# pepper-8m.net
KiCad netlist of a schematic drawn in EAGLE
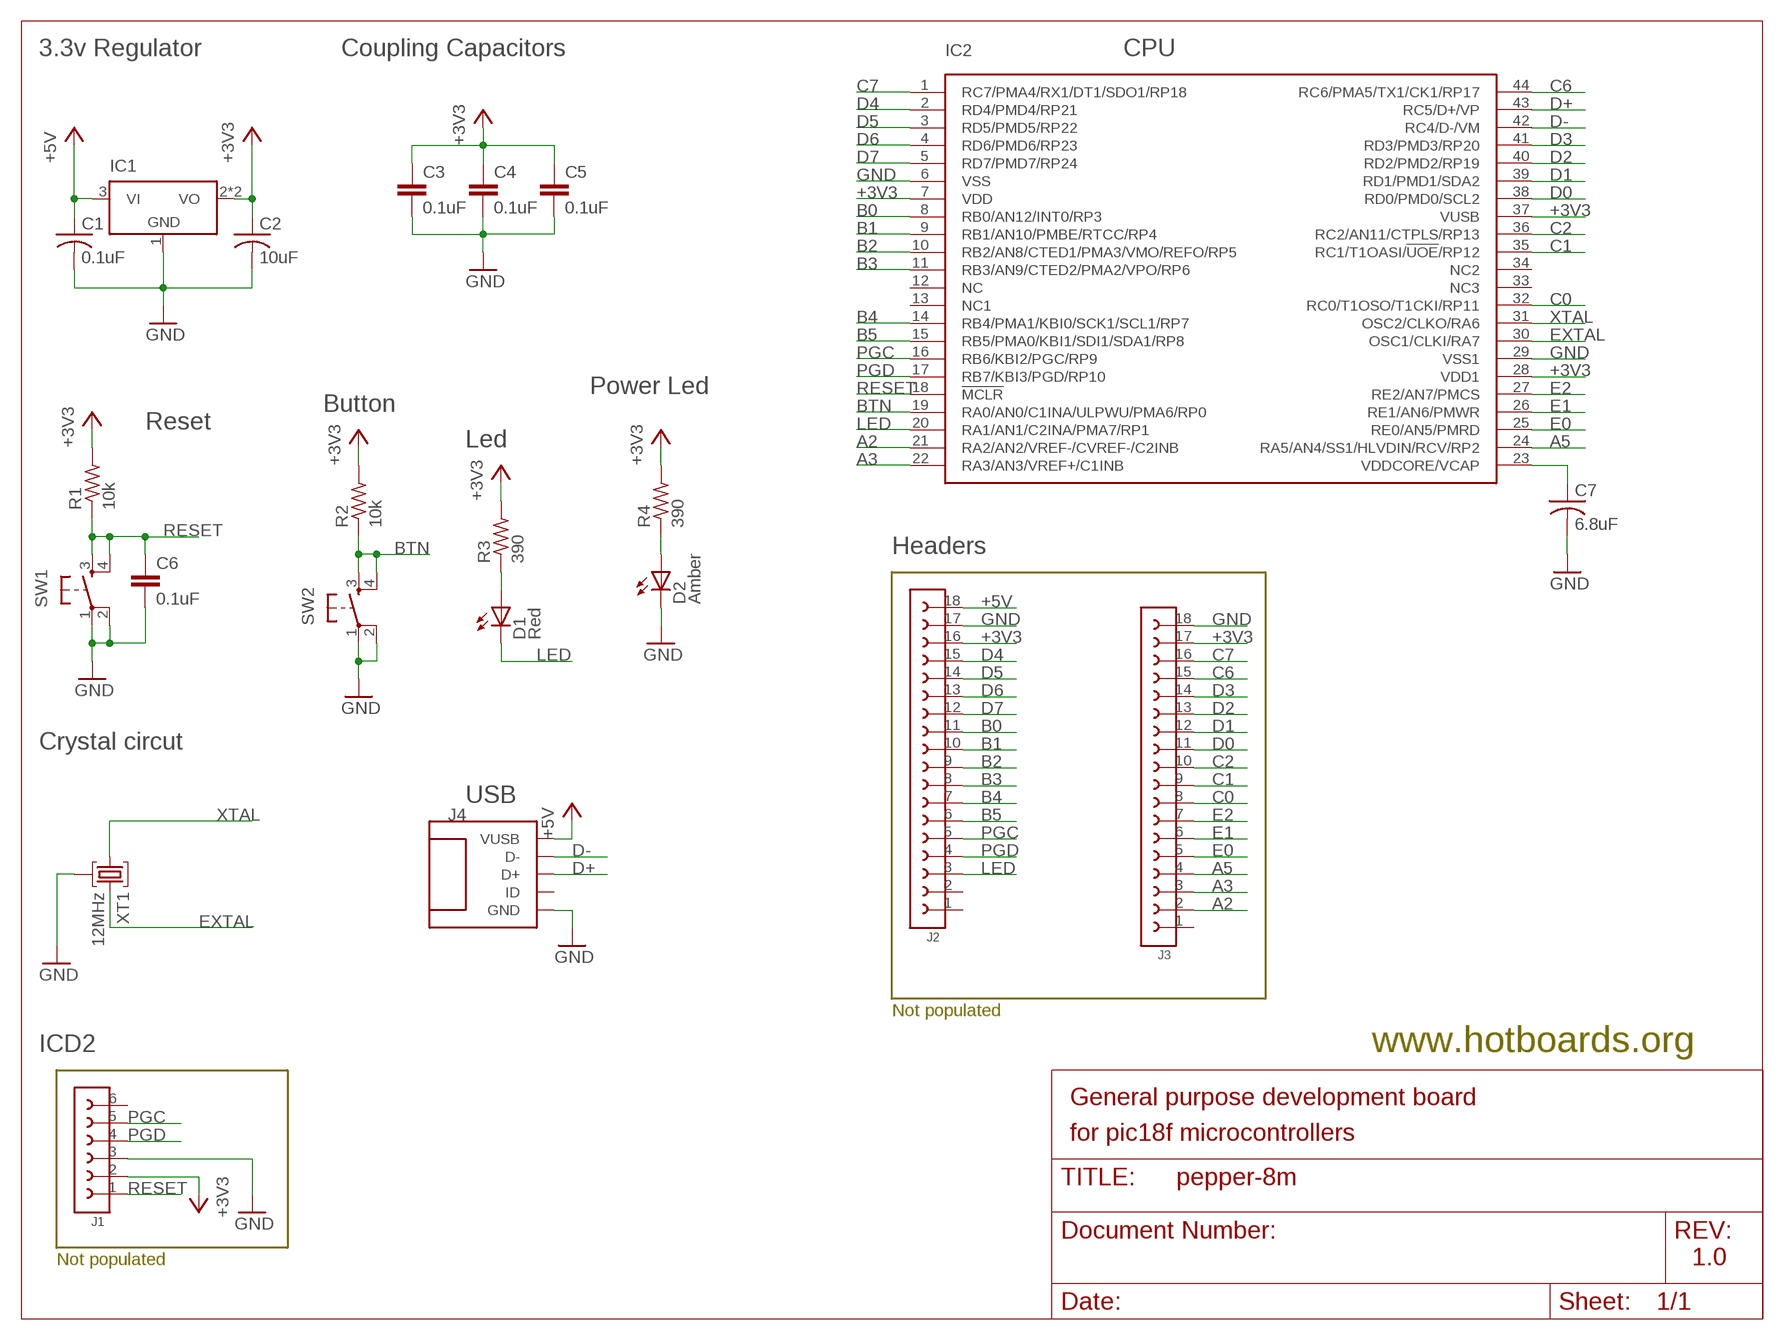
[diagram p0: schematic, sheet 1]

(export (version "E")
  (design (tool "Eeschema 10.0.6"))
  (components
    (comp (ref "C1")
      (value "0.1uF")
      (footprint "eagle-import:CAPMP3216-18")
      (fields (field (name "MANUFACTURER") "KEMET") (field (name "EAGLEUP") "CAPMP3216-18"))
      (libsource (lib "eagle-import") (part "T491?A104K050AT"))
    )
    (comp (ref "C2")
      (value "10uF")
      (footprint "eagle-import:CAPMP3216-18")
      (fields (field (name "MANUFACTURER") "KEMET") (field (name "EAGLEUP") "CAPMP3216-18"))
      (libsource (lib "eagle-import") (part "T491?A106K016AT"))
    )
    (comp (ref "C3")
      (value "0.1uF")
      (footprint "eagle-import:CAPC0603")
      (fields (field (name "MANUFACTURER") "KEMET"))
      (libsource (lib "eagle-import") (part "C?CVAC0603104Z3"))
    )
    (comp (ref "C4")
      (value "0.1uF")
      (footprint "eagle-import:CAPC0603")
      (fields (field (name "MANUFACTURER") "KEMET"))
      (libsource (lib "eagle-import") (part "C?CVAC0603104Z3"))
    )
    (comp (ref "C5")
      (value "0.1uF")
      (footprint "eagle-import:CAPC0603")
      (fields (field (name "MANUFACTURER") "KEMET"))
      (libsource (lib "eagle-import") (part "C?CVAC0603104Z3"))
    )
    (comp (ref "C6")
      (value "0.1uF")
      (footprint "eagle-import:CAPC0603")
      (description "Capacitores cerámicos de capas múltiples (MLCC) - SMD/SMT0603 25volts 0.1uF Y5V -20+80%")
      (fields
        (field (name "MANUFACTURER") "KEMET")
        (field (name "AVNET") "C0603C104Z3VAC TU")
        (field (name "AVRG-PRICE") "0.1")
        (field (name "DIGIKEY") "399-1100-2-ND")
        (field (name "EAGLEUP") "CAPC0603")
        (field (name "MANUFACTURER_1") "KEMET")
        (field (name "MOUSER") "80-C0603C104Z3V")
        (field (name "NEWARK") "31C9013")
        (field (name "OCTOPART-LINK") "http://octopart.com/c0603c104z3vactu-kemet-98662")
      )
      (libsource (lib "eagle-import") (part "C?CVAC0603104Z3"))
    )
    (comp (ref "C7")
      (value "6.8uF")
      (footprint "eagle-import:CAPMP3216-18")
      (fields (field (name "MANUFACTURER") "KEMET") (field (name "EAGLEUP") "CAPMP3216-18"))
      (libsource (lib "eagle-import") (part "T491?A685M006AT"))
    )
    (comp (ref "D1")
      (value "Red")
      (footprint "eagle-import:D0805")
      (libsource (lib "eagle-import") (part "SM0805AC"))
    )
    (comp (ref "D2")
      (value "Amber")
      (footprint "eagle-import:D0805")
      (libsource (lib "eagle-import") (part "SM0805HC"))
    )
    (comp (ref "IC1")
      (value "LD1117S33TR")
      (footprint "eagle-import:SOT230P700X180-4N")
      (fields (field (name "MANUFACTURER") "ST") (field (name "EAGLEUP") "SOT230P700X180-4N"))
      (libsource (lib "eagle-import") (part "LD1117?S33TR"))
    )
    (comp (ref "IC2")
      (value "PIC18F45J50-I/PT'")
      (footprint "eagle-import:TQFP80P1200X1200X100-44N")
      (fields (field (name "MANUFACTURER") "MICROCHIP") (field (name "EAGLEUP") "QFP80P1200X1200X100-44N"))
      (libsource (lib "eagle-import") (part "PIC18F4J50-I/PT'5"))
    )
    (comp (ref "J1")
      (value "61300611121")
      (footprint "eagle-import:PHSP254P1524X254X1154-6S")
      (fields (field (name "MANUFACTURER") "WURTH") (field (name "EAGLEUP") "PHSP254P1524X254X1154-6S"))
      (libsource (lib "eagle-import") (part "6130061?1121"))
    )
    (comp (ref "J2")
      (value "61301811121")
      (footprint "eagle-import:PHSP254P4572X254X1154-18S")
      (libsource (lib "eagle-import") (part "6130181?1121"))
    )
    (comp (ref "J3")
      (value "61301811121")
      (footprint "eagle-import:PHSP254P4572X254X1154-18S")
      (libsource (lib "eagle-import") (part "6130181?1121"))
    )
    (comp (ref "J4")
      (value "-1734035-1")
      (footprint "eagle-import:USB-MINIB-SMD+SMD+RET")
      (libsource (lib "eagle-import") (part "?-1734035-1"))
    )
    (comp (ref "R1")
      (value "10k")
      (footprint "eagle-import:RESC0603")
      (libsource (lib "eagle-import") (part "CRG?0603F10K10"))
    )
    (comp (ref "R2")
      (value "10k")
      (footprint "eagle-import:RESC0603")
      (libsource (lib "eagle-import") (part "CRG?0603F10K10"))
    )
    (comp (ref "R3")
      (value "390")
      (footprint "eagle-import:RESC0603")
      (libsource (lib "eagle-import") (part "CRG?0603F390R"))
    )
    (comp (ref "R4")
      (value "390")
      (footprint "eagle-import:RESC0603")
      (libsource (lib "eagle-import") (part "CRG?0603F390R"))
    )
    (comp (ref "SW1")
      (value "TL3301NF160QJ")
      (footprint "eagle-import:TACT600X600-4J")
      (fields (field (name "MANUFACTURER") "E-SWITCH"))
      (libsource (lib "eagle-import") (part "TL3301?JNF160Q"))
    )
    (comp (ref "SW2")
      (value "TL3301NF160QJ")
      (footprint "eagle-import:TACT600X600-4J")
      (fields (field (name "MANUFACTURER") "E-SWITCH"))
      (libsource (lib "eagle-import") (part "TL3301?JNF160Q"))
    )
    (comp (ref "XT1")
      (value "12MHz")
      (footprint "eagle-import:CERAMIC460X200-3N")
      (fields (field (name "MANUFACTURER") "ABRACON"))
      (libsource (lib "eagle-import") (part "AWSCR-CR-C12.00"))
    )
  )
  (nets
    (net (code "1") (name "+3V3") (class "Default")
      (node (ref "C2") (pin "1") (pinfunction "1_1") (pintype "passive"))
      (node (ref "C3") (pin "1") (pinfunction "1_1") (pintype "passive"))
      (node (ref "C4") (pin "1") (pinfunction "1_1") (pintype "passive"))
      (node (ref "C5") (pin "1") (pinfunction "1_1") (pintype "passive"))
      (node (ref "IC1") (pin "2") (pinfunction "VO_2") (pintype "input"))
      (node (ref "IC1") (pin "4") (pinfunction "VO_4") (pintype "input"))
      (node (ref "IC2") (pin "28") (pinfunction "VDD1_28") (pintype "power_in"))
      (node (ref "IC2") (pin "37") (pinfunction "VUSB_37") (pintype "power_in"))
      (node (ref "IC2") (pin "7") (pinfunction "VDD_7") (pintype "power_in"))
      (node (ref "J1") (pin "2") (pinfunction "2_2") (pintype "passive"))
      (node (ref "J2") (pin "16") (pinfunction "16_16") (pintype "passive"))
      (node (ref "J3") (pin "17") (pinfunction "17_17") (pintype "passive"))
      (node (ref "R1") (pin "P$2") (pinfunction "2_P$2") (pintype "passive"))
      (node (ref "R2") (pin "P$2") (pinfunction "2_P$2") (pintype "passive"))
      (node (ref "R3") (pin "P$2") (pinfunction "2_P$2") (pintype "passive"))
      (node (ref "R4") (pin "P$2") (pinfunction "2_P$2") (pintype "passive"))
    )
    (net (code "2") (name "+5V") (class "Default")
      (node (ref "C1") (pin "1") (pinfunction "1_1") (pintype "passive"))
      (node (ref "IC1") (pin "3") (pinfunction "VI_3") (pintype "input"))
      (node (ref "J2") (pin "18") (pinfunction "18_18") (pintype "passive"))
      (node (ref "J4") (pin "1") (pinfunction "VUSB_1") (pintype "bidirectional"))
    )
    (net (code "3") (name "/A2") (class "Default")
      (node (ref "IC2") (pin "21") (pinfunction "RA2/AN2/VREF-/CVREF-/C2INB_21") (pintype "bidirectional"))
      (node (ref "J3") (pin "2") (pinfunction "2_2") (pintype "passive"))
    )
    (net (code "4") (name "/A3") (class "Default")
      (node (ref "IC2") (pin "22") (pinfunction "RA3/AN3/VREF+/C1INB_22") (pintype "bidirectional"))
      (node (ref "J3") (pin "3") (pinfunction "3_3") (pintype "passive"))
    )
    (net (code "5") (name "/A5") (class "Default")
      (node (ref "IC2") (pin "24") (pinfunction "RA5/AN4/SS1/HLVDIN/RCV/RP2_24") (pintype "bidirectional"))
      (node (ref "J3") (pin "4") (pinfunction "4_4") (pintype "passive"))
    )
    (net (code "6") (name "/B0") (class "Default")
      (node (ref "IC2") (pin "8") (pinfunction "RB0/AN12/INT0/RP3_8") (pintype "bidirectional"))
      (node (ref "J2") (pin "11") (pinfunction "11_11") (pintype "passive"))
    )
    (net (code "7") (name "/B1") (class "Default")
      (node (ref "IC2") (pin "9") (pinfunction "RB1/AN10/PMBE/RTCC/RP4_9") (pintype "bidirectional"))
      (node (ref "J2") (pin "10") (pinfunction "10_10") (pintype "passive"))
    )
    (net (code "8") (name "/B2") (class "Default")
      (node (ref "IC2") (pin "10") (pinfunction "RB2/AN8/CTED1/PMA3/VMO/REFO/RP5_10") (pintype "bidirectional"))
      (node (ref "J2") (pin "9") (pinfunction "9_9") (pintype "passive"))
    )
    (net (code "9") (name "/B3") (class "Default")
      (node (ref "IC2") (pin "11") (pinfunction "RB3/AN9/CTED2/PMA2/VPO/RP6_11") (pintype "bidirectional"))
      (node (ref "J2") (pin "8") (pinfunction "8_8") (pintype "passive"))
    )
    (net (code "10") (name "/B4") (class "Default")
      (node (ref "IC2") (pin "14") (pinfunction "RB4/PMA1/KBI0/SCK1/SCL1/RP7_14") (pintype "bidirectional"))
      (node (ref "J2") (pin "7") (pinfunction "7_7") (pintype "passive"))
    )
    (net (code "11") (name "/B5") (class "Default")
      (node (ref "IC2") (pin "15") (pinfunction "RB5/PMA0/KBI1/SDI1/SDA1/RP8_15") (pintype "bidirectional"))
      (node (ref "J2") (pin "6") (pinfunction "6_6") (pintype "passive"))
    )
    (net (code "12") (name "/BTN") (class "Default")
      (node (ref "IC2") (pin "19") (pinfunction "RA0/AN0/C1INA/ULPWU/PMA6/RP0_19") (pintype "bidirectional"))
      (node (ref "R2") (pin "P$1") (pinfunction "1_P$1") (pintype "passive"))
      (node (ref "SW2") (pin "3") (pinfunction "S_3") (pintype "passive"))
      (node (ref "SW2") (pin "4") (pinfunction "S1_4") (pintype "passive"))
    )
    (net (code "13") (name "/C0") (class "Default")
      (node (ref "IC2") (pin "32") (pinfunction "RC0/T1OSO/T1CKI/RP11_32") (pintype "bidirectional"))
      (node (ref "J3") (pin "8") (pinfunction "8_8") (pintype "passive"))
    )
    (net (code "14") (name "/C1") (class "Default")
      (node (ref "IC2") (pin "35") (pinfunction "RC1/T1OASI/~{UOE}/RP12_35") (pintype "bidirectional"))
      (node (ref "J3") (pin "9") (pinfunction "9_9") (pintype "passive"))
    )
    (net (code "15") (name "/C2") (class "Default")
      (node (ref "IC2") (pin "36") (pinfunction "RC2/AN11/CTPLS/RP13_36") (pintype "bidirectional"))
      (node (ref "J3") (pin "10") (pinfunction "10_10") (pintype "passive"))
    )
    (net (code "16") (name "/C6") (class "Default")
      (node (ref "IC2") (pin "44") (pinfunction "RC6/PMA5/TX1/CK1/RP17_44") (pintype "bidirectional"))
      (node (ref "J3") (pin "15") (pinfunction "15_15") (pintype "passive"))
    )
    (net (code "17") (name "/C7") (class "Default")
      (node (ref "IC2") (pin "1") (pinfunction "RC7/PMA4/RX1/DT1/SDO1/RP18_1") (pintype "bidirectional"))
      (node (ref "J3") (pin "16") (pinfunction "16_16") (pintype "passive"))
    )
    (net (code "18") (name "/D+") (class "Default")
      (node (ref "IC2") (pin "43") (pinfunction "RC5/D+/VP_43") (pintype "bidirectional"))
      (node (ref "J4") (pin "3") (pinfunction "D+_3") (pintype "bidirectional"))
    )
    (net (code "19") (name "/D-") (class "Default")
      (node (ref "IC2") (pin "42") (pinfunction "RC4/D-/VM_42") (pintype "bidirectional"))
      (node (ref "J4") (pin "2") (pinfunction "D-_2") (pintype "bidirectional"))
    )
    (net (code "20") (name "/D0") (class "Default")
      (node (ref "IC2") (pin "38") (pinfunction "RD0/PMD0/SCL2_38") (pintype "bidirectional"))
      (node (ref "J3") (pin "11") (pinfunction "11_11") (pintype "passive"))
    )
    (net (code "21") (name "/D1") (class "Default")
      (node (ref "IC2") (pin "39") (pinfunction "RD1/PMD1/SDA2_39") (pintype "bidirectional"))
      (node (ref "J3") (pin "12") (pinfunction "12_12") (pintype "passive"))
    )
    (net (code "22") (name "/D2") (class "Default")
      (node (ref "IC2") (pin "40") (pinfunction "RD2/PMD2/RP19_40") (pintype "bidirectional"))
      (node (ref "J3") (pin "13") (pinfunction "13_13") (pintype "passive"))
    )
    (net (code "23") (name "/D3") (class "Default")
      (node (ref "IC2") (pin "41") (pinfunction "RD3/PMD3/RP20_41") (pintype "bidirectional"))
      (node (ref "J3") (pin "14") (pinfunction "14_14") (pintype "passive"))
    )
    (net (code "24") (name "/D4") (class "Default")
      (node (ref "IC2") (pin "2") (pinfunction "RD4/PMD4/RP21_2") (pintype "bidirectional"))
      (node (ref "J2") (pin "15") (pinfunction "15_15") (pintype "passive"))
    )
    (net (code "25") (name "/D5") (class "Default")
      (node (ref "IC2") (pin "3") (pinfunction "RD5/PMD5/RP22_3") (pintype "bidirectional"))
      (node (ref "J2") (pin "14") (pinfunction "14_14") (pintype "passive"))
    )
    (net (code "26") (name "/D6") (class "Default")
      (node (ref "IC2") (pin "4") (pinfunction "RD6/PMD6/RP23_4") (pintype "bidirectional"))
      (node (ref "J2") (pin "13") (pinfunction "13_13") (pintype "passive"))
    )
    (net (code "27") (name "/D7") (class "Default")
      (node (ref "IC2") (pin "5") (pinfunction "RD7/PMD7/RP24_5") (pintype "bidirectional"))
      (node (ref "J2") (pin "12") (pinfunction "12_12") (pintype "passive"))
    )
    (net (code "28") (name "/E0") (class "Default")
      (node (ref "IC2") (pin "25") (pinfunction "RE0/AN5/PMRD_25") (pintype "bidirectional"))
      (node (ref "J3") (pin "5") (pinfunction "5_5") (pintype "passive"))
    )
    (net (code "29") (name "/E1") (class "Default")
      (node (ref "IC2") (pin "26") (pinfunction "RE1/AN6/PMWR_26") (pintype "bidirectional"))
      (node (ref "J3") (pin "6") (pinfunction "6_6") (pintype "passive"))
    )
    (net (code "30") (name "/E2") (class "Default")
      (node (ref "IC2") (pin "27") (pinfunction "RE2/AN7/PMCS_27") (pintype "bidirectional"))
      (node (ref "J3") (pin "7") (pinfunction "7_7") (pintype "passive"))
    )
    (net (code "31") (name "/EXTAL") (class "Default")
      (node (ref "IC2") (pin "30") (pinfunction "OSC1/CLKI/RA7_30") (pintype "bidirectional"))
      (node (ref "XT1") (pin "3") (pinfunction "3_3") (pintype "passive"))
    )
    (net (code "32") (name "/LED") (class "Default")
      (node (ref "D1") (pin "2") (pinfunction "C_2") (pintype "passive"))
      (node (ref "IC2") (pin "20") (pinfunction "RA1/AN1/C2INA/PMA7/RP1_20") (pintype "bidirectional"))
      (node (ref "J2") (pin "3") (pinfunction "3_3") (pintype "passive"))
    )
    (net (code "33") (name "/PGC") (class "Default")
      (node (ref "IC2") (pin "16") (pinfunction "RB6/KBI2/PGC/RP9_16") (pintype "bidirectional"))
      (node (ref "J1") (pin "5") (pinfunction "5_5") (pintype "passive"))
      (node (ref "J2") (pin "5") (pinfunction "5_5") (pintype "passive"))
    )
    (net (code "34") (name "/PGD") (class "Default")
      (node (ref "IC2") (pin "17") (pinfunction "RB7/KBI3/PGD/RP10_17") (pintype "bidirectional"))
      (node (ref "J1") (pin "4") (pinfunction "4_4") (pintype "passive"))
      (node (ref "J2") (pin "4") (pinfunction "4_4") (pintype "passive"))
    )
    (net (code "35") (name "/RESET") (class "Default")
      (node (ref "C6") (pin "1") (pinfunction "1_1") (pintype "passive"))
      (node (ref "IC2") (pin "18") (pinfunction "~{MCLR}_18") (pintype "bidirectional"))
      (node (ref "J1") (pin "1") (pinfunction "1_1") (pintype "passive"))
      (node (ref "R1") (pin "P$1") (pinfunction "1_P$1") (pintype "passive"))
      (node (ref "SW1") (pin "3") (pinfunction "S_3") (pintype "passive"))
      (node (ref "SW1") (pin "4") (pinfunction "S1_4") (pintype "passive"))
    )
    (net (code "36") (name "/XTAL") (class "Default")
      (node (ref "IC2") (pin "31") (pinfunction "OSC2/CLKO/RA6_31") (pintype "bidirectional"))
      (node (ref "XT1") (pin "1") (pinfunction "1_1") (pintype "passive"))
    )
    (net (code "37") (name "GND") (class "Default")
      (node (ref "C1") (pin "2") (pinfunction "2_2") (pintype "passive"))
      (node (ref "C2") (pin "2") (pinfunction "2_2") (pintype "passive"))
      (node (ref "C3") (pin "2") (pinfunction "2_2") (pintype "passive"))
      (node (ref "C4") (pin "2") (pinfunction "2_2") (pintype "passive"))
      (node (ref "C5") (pin "2") (pinfunction "2_2") (pintype "passive"))
      (node (ref "C6") (pin "2") (pinfunction "2_2") (pintype "passive"))
      (node (ref "C7") (pin "2") (pinfunction "2_2") (pintype "passive"))
      (node (ref "D2") (pin "2") (pinfunction "C_2") (pintype "passive"))
      (node (ref "IC1") (pin "1") (pinfunction "GND_1") (pintype "power_in"))
      (node (ref "IC2") (pin "29") (pinfunction "VSS1_29") (pintype "power_in"))
      (node (ref "IC2") (pin "6") (pinfunction "VSS_6") (pintype "power_in"))
      (node (ref "J1") (pin "3") (pinfunction "3_3") (pintype "passive"))
      (node (ref "J2") (pin "17") (pinfunction "17_17") (pintype "passive"))
      (node (ref "J3") (pin "18") (pinfunction "18_18") (pintype "passive"))
      (node (ref "J4") (pin "5") (pinfunction "GND_5") (pintype "bidirectional"))
      (node (ref "SW1") (pin "1") (pinfunction "P_1") (pintype "passive"))
      (node (ref "SW1") (pin "2") (pinfunction "P1_2") (pintype "passive"))
      (node (ref "SW2") (pin "1") (pinfunction "P_1") (pintype "passive"))
      (node (ref "SW2") (pin "2") (pinfunction "P1_2") (pintype "passive"))
      (node (ref "XT1") (pin "2") (pinfunction "2_2") (pintype "passive"))
    )
    (net (code "38") (name "Net-(D1-A)") (class "Default")
      (node (ref "D1") (pin "1") (pinfunction "A_1") (pintype "passive"))
      (node (ref "R3") (pin "P$1") (pinfunction "1_P$1") (pintype "passive"))
    )
    (net (code "39") (name "Net-(D2-A)") (class "Default")
      (node (ref "D2") (pin "1") (pinfunction "A_1") (pintype "passive"))
      (node (ref "R4") (pin "P$1") (pinfunction "1_P$1") (pintype "passive"))
    )
    (net (code "40") (name "Net-(IC2-VDDCORE{slash}VCAP)") (class "Default")
      (node (ref "C7") (pin "1") (pinfunction "1_1") (pintype "passive"))
      (node (ref "IC2") (pin "23") (pinfunction "VDDCORE/VCAP_23") (pintype "power_in"))
    )
    (net (code "41") (name "unconnected-(IC2-NC-Pad12)") (class "Default")
      (node (ref "IC2") (pin "12") (pinfunction "NC_12") (pintype "bidirectional"))
    )
    (net (code "42") (name "unconnected-(IC2-NC1-Pad13)") (class "Default")
      (node (ref "IC2") (pin "13") (pinfunction "NC1_13") (pintype "bidirectional"))
    )
    (net (code "43") (name "unconnected-(IC2-NC2-Pad34)") (class "Default")
      (node (ref "IC2") (pin "34") (pinfunction "NC2_34") (pintype "bidirectional"))
    )
    (net (code "44") (name "unconnected-(IC2-NC3-Pad33)") (class "Default")
      (node (ref "IC2") (pin "33") (pinfunction "NC3_33") (pintype "bidirectional"))
    )
    (net (code "45") (name "unconnected-(J1-Pad6)") (class "Default")
      (node (ref "J1") (pin "6") (pinfunction "6_6") (pintype "passive"))
    )
    (net (code "46") (name "unconnected-(J2-Pad1)") (class "Default")
      (node (ref "J2") (pin "1") (pinfunction "1_1") (pintype "passive"))
    )
    (net (code "47") (name "unconnected-(J2-Pad2)") (class "Default")
      (node (ref "J2") (pin "2") (pinfunction "2_2") (pintype "passive"))
    )
    (net (code "48") (name "unconnected-(J3-Pad1)") (class "Default")
      (node (ref "J3") (pin "1") (pinfunction "1_1") (pintype "passive"))
    )
    (net (code "49") (name "unconnected-(J4-ID-Pad4)") (class "Default")
      (node (ref "J4") (pin "4") (pinfunction "ID_4") (pintype "bidirectional"))
    )
  )
)
